# untitled.net
KiCad netlist of a schematic drawn in EAGLE
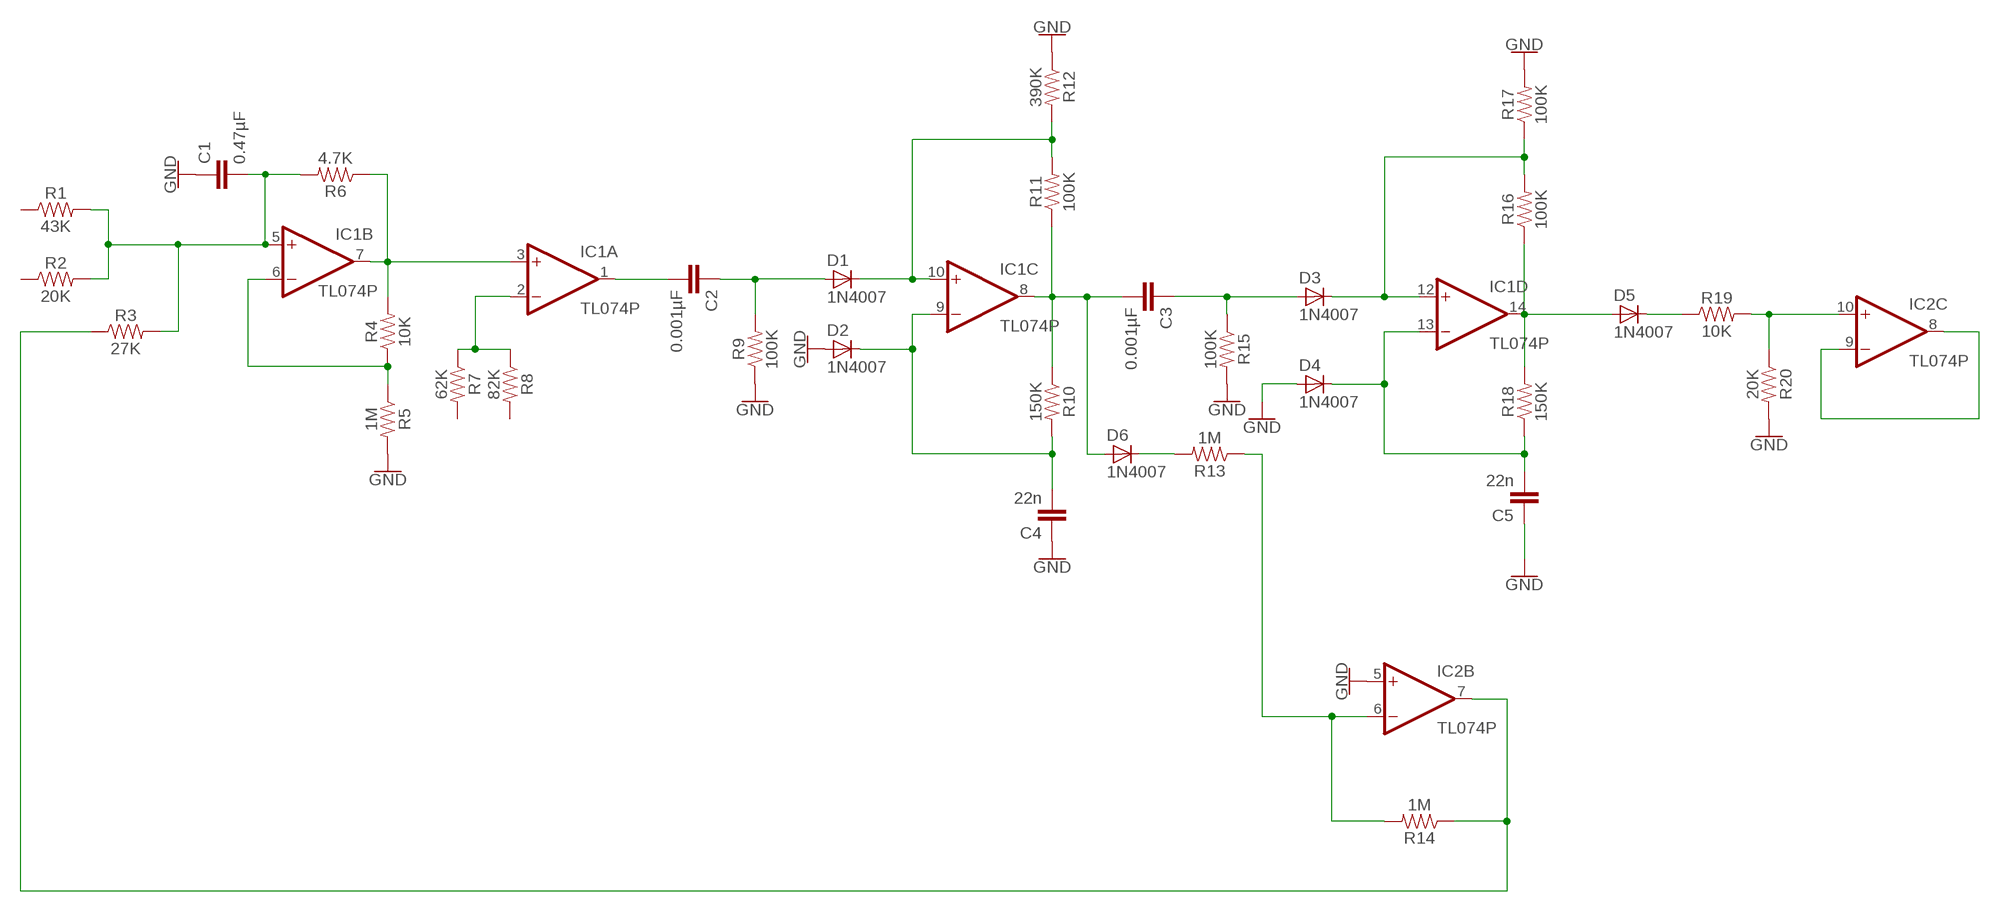
[diagram p0: schematic, sheet 1]

(export (version "E")
  (design (tool "Eeschema 10.0.6"))
  (components
    (comp (ref "C1")
      (value "0.47µF")
      (footprint "eagle-import:0805")
      (libsource (lib "eagle-import") (part "0.33UF/330NF-0805-50V-10%"))
    )
    (comp (ref "C2")
      (value "0.001µF")
      (footprint "eagle-import:0805")
      (libsource (lib "eagle-import") (part "0.33UF/330NF-0805-50V-10%"))
    )
    (comp (ref "C3")
      (value "0.001µF")
      (footprint "eagle-import:0805")
      (libsource (lib "eagle-import") (part "0.33UF/330NF-0805-50V-10%"))
    )
    (comp (ref "C4")
      (value "22n")
      (footprint "eagle-import:0805")
      (libsource (lib "eagle-import") (part "0.33UF/330NF-0805-50V-10%"))
    )
    (comp (ref "C5")
      (value "22n")
      (footprint "eagle-import:0805")
      (libsource (lib "eagle-import") (part "0.33UF/330NF-0805-50V-10%"))
    )
    (comp (ref "D1")
      (value "1N4007")
      (footprint "eagle-import:SMA")
      (libsource (lib "eagle-import") (part "1N4007"))
    )
    (comp (ref "D2")
      (value "1N4007")
      (footprint "eagle-import:SMA")
      (libsource (lib "eagle-import") (part "1N4007"))
    )
    (comp (ref "D3")
      (value "1N4007")
      (footprint "eagle-import:SMA")
      (libsource (lib "eagle-import") (part "1N4007"))
    )
    (comp (ref "D4")
      (value "1N4007")
      (footprint "eagle-import:SMA")
      (libsource (lib "eagle-import") (part "1N4007"))
    )
    (comp (ref "D5")
      (value "1N4007")
      (footprint "eagle-import:SMA")
      (libsource (lib "eagle-import") (part "1N4007"))
    )
    (comp (ref "D6")
      (value "1N4007")
      (footprint "eagle-import:SMA")
      (libsource (lib "eagle-import") (part "1N4007"))
    )
    (comp (ref "IC1")
      (value "TL074P")
      (footprint "eagle-import:DIL14")
      (libsource (lib "eagle-import") (part "TL074P"))
    )
    (comp (ref "IC2")
      (value "TL074P")
      (footprint "eagle-import:DIL14")
      (libsource (lib "eagle-import") (part "TL074P"))
    )
    (comp (ref "R1")
      (value "43K")
      (footprint "eagle-import:0805")
      (libsource (lib "eagle-import") (part "0.3OHM-0805-1/8W-1%"))
    )
    (comp (ref "R2")
      (value "20K")
      (footprint "eagle-import:0805")
      (libsource (lib "eagle-import") (part "0.3OHM-0805-1/8W-1%"))
    )
    (comp (ref "R3")
      (value "27K")
      (footprint "eagle-import:0805")
      (libsource (lib "eagle-import") (part "0.3OHM-0805-1/8W-1%"))
    )
    (comp (ref "R4")
      (value "10K")
      (footprint "eagle-import:0805")
      (libsource (lib "eagle-import") (part "0.3OHM-0805-1/8W-1%"))
    )
    (comp (ref "R5")
      (value "1M")
      (footprint "eagle-import:0805")
      (libsource (lib "eagle-import") (part "0.3OHM-0805-1/8W-1%"))
    )
    (comp (ref "R6")
      (value "4.7K")
      (footprint "eagle-import:0805")
      (libsource (lib "eagle-import") (part "0.3OHM-0805-1/8W-1%"))
    )
    (comp (ref "R7")
      (value "62K")
      (footprint "eagle-import:0805")
      (libsource (lib "eagle-import") (part "0.3OHM-0805-1/8W-1%"))
    )
    (comp (ref "R8")
      (value "82K")
      (footprint "eagle-import:0805")
      (libsource (lib "eagle-import") (part "0.3OHM-0805-1/8W-1%"))
    )
    (comp (ref "R9")
      (value "100K")
      (footprint "eagle-import:0805")
      (libsource (lib "eagle-import") (part "0.3OHM-0805-1/8W-1%"))
    )
    (comp (ref "R10")
      (value "150K")
      (footprint "eagle-import:0805")
      (libsource (lib "eagle-import") (part "0.3OHM-0805-1/8W-1%"))
    )
    (comp (ref "R11")
      (value "100K")
      (footprint "eagle-import:0805")
      (libsource (lib "eagle-import") (part "0.3OHM-0805-1/8W-1%"))
    )
    (comp (ref "R12")
      (value "390K")
      (footprint "eagle-import:0805")
      (libsource (lib "eagle-import") (part "0.3OHM-0805-1/8W-1%"))
    )
    (comp (ref "R13")
      (value "1M")
      (footprint "eagle-import:0805")
      (libsource (lib "eagle-import") (part "0.3OHM-0805-1/8W-1%"))
    )
    (comp (ref "R14")
      (value "1M")
      (footprint "eagle-import:0805")
      (libsource (lib "eagle-import") (part "0.3OHM-0805-1/8W-1%"))
    )
    (comp (ref "R15")
      (value "100K")
      (footprint "eagle-import:0805")
      (libsource (lib "eagle-import") (part "0.3OHM-0805-1/8W-1%"))
    )
    (comp (ref "R16")
      (value "100K")
      (footprint "eagle-import:0805")
      (libsource (lib "eagle-import") (part "0.3OHM-0805-1/8W-1%"))
    )
    (comp (ref "R17")
      (value "100K")
      (footprint "eagle-import:0805")
      (libsource (lib "eagle-import") (part "0.3OHM-0805-1/8W-1%"))
    )
    (comp (ref "R18")
      (value "150K")
      (footprint "eagle-import:0805")
      (libsource (lib "eagle-import") (part "0.3OHM-0805-1/8W-1%"))
    )
    (comp (ref "R19")
      (value "10K")
      (footprint "eagle-import:0805")
      (libsource (lib "eagle-import") (part "0.3OHM-0805-1/8W-1%"))
    )
    (comp (ref "R20")
      (value "20K")
      (footprint "eagle-import:0805")
      (libsource (lib "eagle-import") (part "0.3OHM-0805-1/8W-1%"))
    )
  )
  (nets
    (net (code "1") (name "GND") (class "Default")
      (node (ref "C1") (pin "1") (pinfunction "1_1") (pintype "passive"))
      (node (ref "C4") (pin "1") (pinfunction "1_1") (pintype "passive"))
      (node (ref "C5") (pin "1") (pinfunction "1_1") (pintype "passive"))
      (node (ref "D2") (pin "A") (pinfunction "A_A") (pintype "passive"))
      (node (ref "D4") (pin "A") (pinfunction "A_A") (pintype "passive"))
      (node (ref "IC2") (pin "5") (pinfunction "+IN_5") (pintype "input"))
      (node (ref "R12") (pin "1") (pinfunction "1_1") (pintype "passive"))
      (node (ref "R15") (pin "2") (pinfunction "2_2") (pintype "passive"))
      (node (ref "R17") (pin "2") (pinfunction "2_2") (pintype "passive"))
      (node (ref "R20") (pin "2") (pinfunction "2_2") (pintype "passive"))
      (node (ref "R5") (pin "2") (pinfunction "2_2") (pintype "passive"))
      (node (ref "R9") (pin "1") (pinfunction "1_1") (pintype "passive"))
    )
    (net (code "2") (name "Net-(C2-Pad1)") (class "Default")
      (node (ref "C2") (pin "1") (pinfunction "1_1") (pintype "passive"))
      (node (ref "D1") (pin "A") (pinfunction "A_A") (pintype "passive"))
      (node (ref "R9") (pin "2") (pinfunction "2_2") (pintype "passive"))
    )
    (net (code "3") (name "Net-(C3-Pad1)") (class "Default")
      (node (ref "C3") (pin "1") (pinfunction "1_1") (pintype "passive"))
      (node (ref "D3") (pin "A") (pinfunction "A_A") (pintype "passive"))
      (node (ref "R15") (pin "1") (pinfunction "1_1") (pintype "passive"))
    )
    (net (code "4") (name "Net-(D1-C)") (class "Default")
      (node (ref "D1") (pin "K") (pinfunction "C_K") (pintype "passive"))
      (node (ref "IC1") (pin "10") (pinfunction "+IN_10") (pintype "input"))
      (node (ref "R11") (pin "2") (pinfunction "2_2") (pintype "passive"))
      (node (ref "R12") (pin "2") (pinfunction "2_2") (pintype "passive"))
    )
    (net (code "5") (name "Net-(D2-C)") (class "Default")
      (node (ref "C4") (pin "2") (pinfunction "2_2") (pintype "passive"))
      (node (ref "D2") (pin "K") (pinfunction "C_K") (pintype "passive"))
      (node (ref "IC1") (pin "9") (pinfunction "-IN_9") (pintype "input"))
      (node (ref "R10") (pin "2") (pinfunction "2_2") (pintype "passive"))
    )
    (net (code "6") (name "Net-(D3-C)") (class "Default")
      (node (ref "D3") (pin "K") (pinfunction "C_K") (pintype "passive"))
      (node (ref "IC1") (pin "12") (pinfunction "+IN_12") (pintype "input"))
      (node (ref "R16") (pin "2") (pinfunction "2_2") (pintype "passive"))
      (node (ref "R17") (pin "1") (pinfunction "1_1") (pintype "passive"))
    )
    (net (code "7") (name "Net-(D4-C)") (class "Default")
      (node (ref "C5") (pin "2") (pinfunction "2_2") (pintype "passive"))
      (node (ref "D4") (pin "K") (pinfunction "C_K") (pintype "passive"))
      (node (ref "IC1") (pin "13") (pinfunction "-IN_13") (pintype "input"))
      (node (ref "R18") (pin "1") (pinfunction "1_1") (pintype "passive"))
    )
    (net (code "8") (name "Net-(D5-C)") (class "Default")
      (node (ref "D5") (pin "K") (pinfunction "C_K") (pintype "passive"))
      (node (ref "R19") (pin "1") (pinfunction "1_1") (pintype "passive"))
    )
    (net (code "9") (name "Net-(D6-C)") (class "Default")
      (node (ref "D6") (pin "K") (pinfunction "C_K") (pintype "passive"))
      (node (ref "R13") (pin "2") (pinfunction "2_2") (pintype "passive"))
    )
    (net (code "10") (name "Net-(IC1A-+IN)") (class "Default")
      (node (ref "IC1") (pin "3") (pinfunction "+IN_3") (pintype "input"))
      (node (ref "IC1") (pin "7") (pinfunction "OUT_7") (pintype "output"))
      (node (ref "R4") (pin "2") (pinfunction "2_2") (pintype "passive"))
      (node (ref "R6") (pin "1") (pinfunction "1_1") (pintype "passive"))
    )
    (net (code "11") (name "Net-(IC1A--IN)") (class "Default")
      (node (ref "IC1") (pin "2") (pinfunction "-IN_2") (pintype "input"))
      (node (ref "R7") (pin "1") (pinfunction "1_1") (pintype "passive"))
      (node (ref "R8") (pin "1") (pinfunction "1_1") (pintype "passive"))
    )
    (net (code "12") (name "Net-(IC1A-OUT)") (class "Default")
      (node (ref "C2") (pin "2") (pinfunction "2_2") (pintype "passive"))
      (node (ref "IC1") (pin "1") (pinfunction "OUT_1") (pintype "output"))
    )
    (net (code "13") (name "Net-(IC1B-+IN)") (class "Default")
      (node (ref "C1") (pin "2") (pinfunction "2_2") (pintype "passive"))
      (node (ref "IC1") (pin "5") (pinfunction "+IN_5") (pintype "input"))
      (node (ref "R1") (pin "2") (pinfunction "2_2") (pintype "passive"))
      (node (ref "R2") (pin "2") (pinfunction "2_2") (pintype "passive"))
      (node (ref "R3") (pin "2") (pinfunction "2_2") (pintype "passive"))
      (node (ref "R6") (pin "2") (pinfunction "2_2") (pintype "passive"))
    )
    (net (code "14") (name "Net-(IC1B--IN)") (class "Default")
      (node (ref "IC1") (pin "6") (pinfunction "-IN_6") (pintype "input"))
      (node (ref "R4") (pin "1") (pinfunction "1_1") (pintype "passive"))
      (node (ref "R5") (pin "1") (pinfunction "1_1") (pintype "passive"))
    )
    (net (code "15") (name "Net-(IC1C-OUT)") (class "Default")
      (node (ref "C3") (pin "2") (pinfunction "2_2") (pintype "passive"))
      (node (ref "D6") (pin "A") (pinfunction "A_A") (pintype "passive"))
      (node (ref "IC1") (pin "8") (pinfunction "OUT_8") (pintype "output"))
      (node (ref "R10") (pin "1") (pinfunction "1_1") (pintype "passive"))
      (node (ref "R11") (pin "1") (pinfunction "1_1") (pintype "passive"))
    )
    (net (code "16") (name "Net-(IC1D-OUT)") (class "Default")
      (node (ref "D5") (pin "A") (pinfunction "A_A") (pintype "passive"))
      (node (ref "IC1") (pin "14") (pinfunction "OUT_14") (pintype "output"))
      (node (ref "R16") (pin "1") (pinfunction "1_1") (pintype "passive"))
      (node (ref "R18") (pin "2") (pinfunction "2_2") (pintype "passive"))
    )
    (net (code "17") (name "Net-(IC2B--IN)") (class "Default")
      (node (ref "IC2") (pin "6") (pinfunction "-IN_6") (pintype "input"))
      (node (ref "R13") (pin "1") (pinfunction "1_1") (pintype "passive"))
      (node (ref "R14") (pin "2") (pinfunction "2_2") (pintype "passive"))
    )
    (net (code "18") (name "Net-(IC2B-OUT)") (class "Default")
      (node (ref "IC2") (pin "7") (pinfunction "OUT_7") (pintype "output"))
      (node (ref "R14") (pin "1") (pinfunction "1_1") (pintype "passive"))
      (node (ref "R3") (pin "1") (pinfunction "1_1") (pintype "passive"))
    )
    (net (code "19") (name "Net-(IC2C-+IN)") (class "Default")
      (node (ref "IC2") (pin "10") (pinfunction "+IN_10") (pintype "input"))
      (node (ref "R19") (pin "2") (pinfunction "2_2") (pintype "passive"))
      (node (ref "R20") (pin "1") (pinfunction "1_1") (pintype "passive"))
    )
    (net (code "20") (name "Net-(IC2C--IN)") (class "Default")
      (node (ref "IC2") (pin "8") (pinfunction "OUT_8") (pintype "output"))
      (node (ref "IC2") (pin "9") (pinfunction "-IN_9") (pintype "input"))
    )
    (net (code "21") (name "unconnected-(R1-Pad1)") (class "Default")
      (node (ref "R1") (pin "1") (pinfunction "1_1") (pintype "passive"))
    )
    (net (code "22") (name "unconnected-(R2-Pad1)") (class "Default")
      (node (ref "R2") (pin "1") (pinfunction "1_1") (pintype "passive"))
    )
    (net (code "23") (name "unconnected-(R7-Pad2)") (class "Default")
      (node (ref "R7") (pin "2") (pinfunction "2_2") (pintype "passive"))
    )
    (net (code "24") (name "unconnected-(R8-Pad2)") (class "Default")
      (node (ref "R8") (pin "2") (pinfunction "2_2") (pintype "passive"))
    )
  )
)
